# schematic.net
KiCad netlist of a schematic drawn in EAGLE
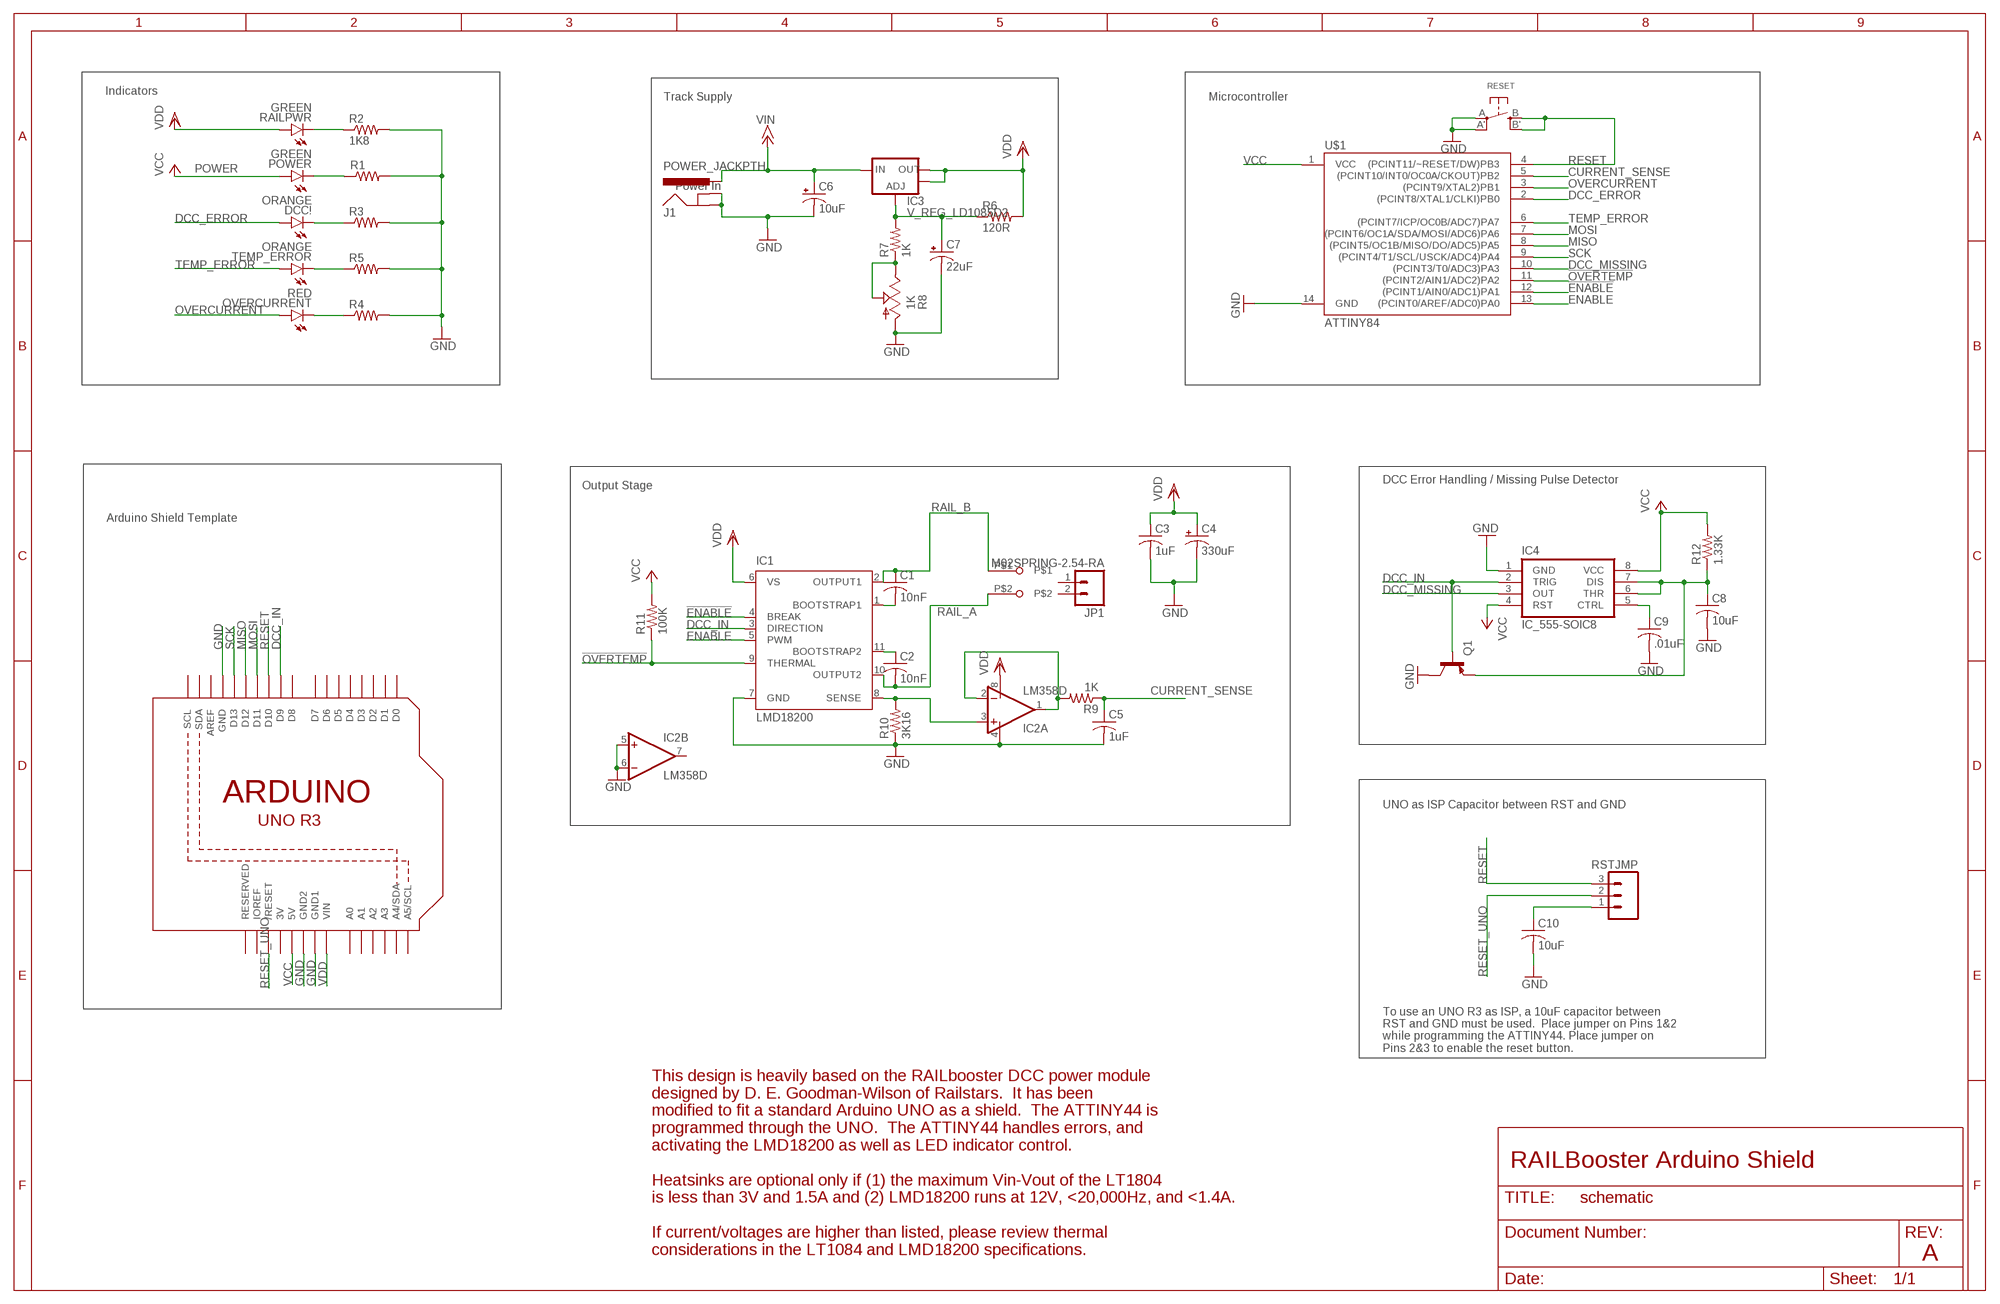
[diagram p0: schematic, sheet 1]

(export (version "E")
  (design (tool "Eeschema 10.0.6"))
  (components
    (comp (ref "C1")
      (value "10nF")
      (footprint "eagle-import:C1206")
      (libsource (lib "eagle-import") (part "C-USC1206"))
    )
    (comp (ref "C2")
      (value "10nF")
      (footprint "eagle-import:C1206")
      (libsource (lib "eagle-import") (part "C-USC1206"))
    )
    (comp (ref "C3")
      (value "1uF")
      (footprint "eagle-import:C1206")
      (libsource (lib "eagle-import") (part "C-USC1206"))
    )
    (comp (ref "C4")
      (value "330uF")
      (footprint "eagle-import:E5-10,5")
      (libsource (lib "eagle-import") (part "CPOL-USE5-10.5"))
    )
    (comp (ref "C5")
      (value "1uF")
      (footprint "eagle-import:C1206")
      (libsource (lib "eagle-import") (part "C-USC1206"))
    )
    (comp (ref "C6")
      (value "10uF")
      (footprint "eagle-import:E2-5")
      (libsource (lib "eagle-import") (part "CPOL-USE2-5"))
    )
    (comp (ref "C7")
      (value "22uF")
      (footprint "eagle-import:E2-5")
      (libsource (lib "eagle-import") (part "CPOL-USE2-5"))
    )
    (comp (ref "C8")
      (value "10uF")
      (footprint "eagle-import:C1206")
      (libsource (lib "eagle-import") (part "C-USC1206"))
    )
    (comp (ref "C9")
      (value ".01uF")
      (footprint "eagle-import:C1206")
      (libsource (lib "eagle-import") (part "C-USC1206"))
    )
    (comp (ref "C10")
      (value "10uF")
      (footprint "eagle-import:C1206")
      (libsource (lib "eagle-import") (part "C-USC1206"))
    )
    (comp (ref "DCC!")
      (value "ORANGE")
      (footprint "eagle-import:LED-1206")
      (libsource (lib "eagle-import") (part "LED1206"))
    )
    (comp (ref "IC1")
      (value "LMD18200")
      (footprint "eagle-import:TO-220-11")
      (libsource (lib "eagle-import") (part "LM18200T"))
    )
    (comp (ref "IC2")
      (value "LM358D")
      (footprint "eagle-import:SO08")
      (libsource (lib "eagle-import") (part "LM358D"))
    )
    (comp (ref "IC3")
      (value "V_REG_LD1085D2")
      (footprint "eagle-import:D2PACK_A")
      (libsource (lib "eagle-import") (part "V_REG_LD1085D2"))
    )
    (comp (ref "IC4")
      (value "IC_555-SOIC8")
      (footprint "eagle-import:SOIC-8")
      (libsource (lib "eagle-import") (part "IC_555-SOIC8"))
    )
    (comp (ref "J1")
      (value "POWER_JACKPTH")
      (footprint "eagle-import:POWER_JACK_PTH")
      (libsource (lib "eagle-import") (part "POWER_JACKPTH"))
    )
    (comp (ref "JP1")
      (value "M02SPRING-2.54-RA")
      (footprint "eagle-import:SPRINGTERMINAL-2.54MM-2")
      (libsource (lib "eagle-import") (part "M02SPRING-2.54-RA"))
    )
    (comp (ref "OVERCURRENT")
      (value "RED")
      (footprint "eagle-import:LED-1206")
      (libsource (lib "eagle-import") (part "LED1206"))
    )
    (comp (ref "POWER")
      (value "GREEN")
      (footprint "eagle-import:LED-1206")
      (libsource (lib "eagle-import") (part "LED1206"))
    )
    (comp (ref "Q1")
      (value "TRANSISTOR_BJT_PNP-SOT-23-BCE")
      (footprint "eagle-import:SOT-23")
      (libsource (lib "eagle-import") (part "TRANSISTOR_BJT_PNP-SOT-23-BCE"))
    )
    (comp (ref "R1")
      (value "RESISTOR1206")
      (footprint "eagle-import:1206")
      (libsource (lib "eagle-import") (part "RESISTOR1206"))
    )
    (comp (ref "R2")
      (value "1K8")
      (footprint "eagle-import:1206")
      (libsource (lib "eagle-import") (part "RESISTOR1206"))
    )
    (comp (ref "R3")
      (value "RESISTOR1206")
      (footprint "eagle-import:1206")
      (libsource (lib "eagle-import") (part "RESISTOR1206"))
    )
    (comp (ref "R4")
      (value "RESISTOR1206")
      (footprint "eagle-import:1206")
      (libsource (lib "eagle-import") (part "RESISTOR1206"))
    )
    (comp (ref "R5")
      (value "RESISTOR1206")
      (footprint "eagle-import:1206")
      (libsource (lib "eagle-import") (part "RESISTOR1206"))
    )
    (comp (ref "R6")
      (value "120R")
      (footprint "eagle-import:1206")
      (libsource (lib "eagle-import") (part "RESISTOR1206"))
    )
    (comp (ref "R7")
      (value "1K")
      (footprint "eagle-import:1206")
      (libsource (lib "eagle-import") (part "RESISTOR1206"))
    )
    (comp (ref "R8")
      (value "1K")
      (footprint "eagle-import:S64W")
      (libsource (lib "eagle-import") (part "TRIM_US-S64W"))
    )
    (comp (ref "R9")
      (value "1K")
      (footprint "eagle-import:1206")
      (libsource (lib "eagle-import") (part "RESISTOR1206"))
    )
    (comp (ref "R10")
      (value "3K16")
      (footprint "eagle-import:1206")
      (libsource (lib "eagle-import") (part "RESISTOR1206"))
    )
    (comp (ref "R11")
      (value "100K")
      (footprint "eagle-import:1206")
      (libsource (lib "eagle-import") (part "RESISTOR1206"))
    )
    (comp (ref "R12")
      (value "1.33K")
      (footprint "eagle-import:1206")
      (libsource (lib "eagle-import") (part "RESISTOR1206"))
    )
    (comp (ref "RAILPWR")
      (value "GREEN")
      (footprint "eagle-import:LED-1206")
      (libsource (lib "eagle-import") (part "LED1206"))
    )
    (comp (ref "RESET")
      (value "SWITCH_TACT_SMT")
      (footprint "eagle-import:EVQ-Q2")
      (libsource (lib "eagle-import") (part "SWITCH_TACT_SMT"))
    )
    (comp (ref "RSTJMP")
      (value "M03PTH")
      (footprint "eagle-import:1X03")
      (libsource (lib "eagle-import") (part "M03PTH"))
    )
    (comp (ref "TEMP_ERROR")
      (value "ORANGE")
      (footprint "eagle-import:LED-1206")
      (libsource (lib "eagle-import") (part "LED1206"))
    )
    (comp (ref "U$1")
      (value "ATTINY84")
      (footprint "eagle-import:SO14")
      (libsource (lib "eagle-import") (part "ATTINY84"))
    )
    (comp (ref "U1")
      (value "ARDUINOR3-DIMENSION")
      (footprint "eagle-import:ARDUINOR3")
      (libsource (lib "eagle-import") (part "ARDUINOR3-DIMENSION"))
    )
    (comp (ref "X4")
      (value "SCREWTERMINAL-5.08-2")
      (footprint "eagle-import:SCREWTERMINAL-5.08-2")
      (libsource (lib "eagle-import") (part "SCREWTERMINAL-5.08-2"))
    )
  )
  (nets
    (net (code "1") (name "/3V") (class "Default")
      (node (ref "U1") (pin "3V") (pinfunction "3V_3V") (pintype "power_in"))
    )
    (net (code "2") (name "/CURRENT_SENSE") (class "Default")
      (node (ref "C5") (pin "1") (pinfunction "1_1") (pintype "passive"))
      (node (ref "R9") (pin "1") (pinfunction "1_1") (pintype "passive"))
      (node (ref "U$1") (pin "5") (pinfunction "(PCINT10/INT0/OC0A/CKOUT)PB2_5") (pintype "bidirectional"))
    )
    (net (code "3") (name "/DCC_ERROR") (class "Default")
      (node (ref "DCC!") (pin "A") (pinfunction "A_A") (pintype "passive"))
      (node (ref "U$1") (pin "2") (pinfunction "(PCINT8/XTAL1/CLKI)PB0_2") (pintype "bidirectional"))
    )
    (net (code "4") (name "/DCC_IN") (class "Default")
      (node (ref "IC1") (pin "3") (pinfunction "DIRECTION_3") (pintype "input"))
      (node (ref "IC4") (pin "2") (pinfunction "TRIG_2") (pintype "input"))
      (node (ref "Q1") (pin "1") (pinfunction "B_1") (pintype "passive"))
      (node (ref "U1") (pin "D9") (pinfunction "D9_D9") (pintype "bidirectional"))
    )
    (net (code "5") (name "/DCC_MISSING") (class "Default")
      (node (ref "IC4") (pin "3") (pinfunction "OUT_3") (pintype "output"))
      (node (ref "U$1") (pin "10") (pinfunction "(PCINT3/T0/ADC3)PA3_10") (pintype "bidirectional"))
    )
    (net (code "6") (name "/ENABLE") (class "Default")
      (node (ref "IC1") (pin "5") (pinfunction "PWM_5") (pintype "input"))
      (node (ref "U$1") (pin "13") (pinfunction "(PCINT0/AREF/ADC0)PA0_13") (pintype "bidirectional"))
    )
    (net (code "7") (name "/MISO") (class "Default")
      (node (ref "U$1") (pin "8") (pinfunction "(PCINT5/OC1B/MISO/DO/ADC5)PA5_8") (pintype "bidirectional"))
      (node (ref "U1") (pin "D12") (pinfunction "D12_D12") (pintype "bidirectional"))
    )
    (net (code "8") (name "/MOSI") (class "Default")
      (node (ref "U$1") (pin "7") (pinfunction "(PCINT6/OC1A/SDA/MOSI/ADC6)PA6_7") (pintype "bidirectional"))
      (node (ref "U1") (pin "D11") (pinfunction "D11_D11") (pintype "bidirectional"))
    )
    (net (code "9") (name "/OVERCURRENT") (class "Default")
      (node (ref "OVERCURRENT") (pin "A") (pinfunction "A_A") (pintype "passive"))
      (node (ref "U$1") (pin "3") (pinfunction "(PCINT9/XTAL2)PB1_3") (pintype "bidirectional"))
    )
    (net (code "10") (name "/RAIL_A") (class "Default")
      (node (ref "C2") (pin "2") (pinfunction "2_2") (pintype "passive"))
      (node (ref "IC1") (pin "10") (pinfunction "OUTPUT2_10") (pintype "output"))
      (node (ref "X4") (pin "P$2") (pinfunction "P$2_P$2") (pintype "bidirectional"))
    )
    (net (code "11") (name "/RAIL_B") (class "Default")
      (node (ref "C1") (pin "1") (pinfunction "1_1") (pintype "passive"))
      (node (ref "IC1") (pin "2") (pinfunction "OUTPUT1_2") (pintype "output"))
      (node (ref "X4") (pin "P$1") (pinfunction "P$1_P$1") (pintype "bidirectional"))
    )
    (net (code "12") (name "/RESET") (class "Default")
      (node (ref "RESET") (pin "B") (pinfunction "S_B") (pintype "passive"))
      (node (ref "RESET") (pin "B'") (pinfunction "S1_B'") (pintype "passive"))
      (node (ref "RSTJMP") (pin "3") (pinfunction "3_3") (pintype "passive"))
      (node (ref "U$1") (pin "4") (pinfunction "(PCINT11/~{RESET/DW})PB3_4") (pintype "bidirectional"))
      (node (ref "U1") (pin "D10") (pinfunction "D10_D10") (pintype "bidirectional"))
    )
    (net (code "13") (name "/RESET_UNO") (class "Default")
      (node (ref "RSTJMP") (pin "2") (pinfunction "2_2") (pintype "passive"))
      (node (ref "U1") (pin "RESET") (pinfunction "/RESET_RESET") (pintype "bidirectional"))
    )
    (net (code "14") (name "/SCK") (class "Default")
      (node (ref "U$1") (pin "9") (pinfunction "(PCINT4/T1/SCL/USCK/ADC4)PA4_9") (pintype "bidirectional"))
      (node (ref "U1") (pin "D13") (pinfunction "D13_D13") (pintype "bidirectional"))
    )
    (net (code "15") (name "/TEMP_ERROR") (class "Default")
      (node (ref "TEMP_ERROR") (pin "A") (pinfunction "A_A") (pintype "passive"))
      (node (ref "U$1") (pin "6") (pinfunction "(PCINT7/ICP/OC0B/ADC7)PA7_6") (pintype "bidirectional"))
    )
    (net (code "16") (name "/~{ENABLE}") (class "Default")
      (node (ref "IC1") (pin "4") (pinfunction "BREAK_4") (pintype "input"))
      (node (ref "U$1") (pin "12") (pinfunction "(PCINT1/AIN0/ADC1)PA1_12") (pintype "bidirectional"))
    )
    (net (code "17") (name "/~{OVERTEMP}") (class "Default")
      (node (ref "IC1") (pin "9") (pinfunction "THERMAL_9") (pintype "output"))
      (node (ref "R11") (pin "1") (pinfunction "1_1") (pintype "passive"))
      (node (ref "U$1") (pin "11") (pinfunction "(PCINT2/AIN1/ADC2)PA2_11") (pintype "bidirectional"))
    )
    (net (code "18") (name "GND") (class "Default")
      (node (ref "C10") (pin "2") (pinfunction "2_2") (pintype "passive"))
      (node (ref "C3") (pin "2") (pinfunction "2_2") (pintype "passive"))
      (node (ref "C4") (pin "-") (pinfunction "-_-") (pintype "passive"))
      (node (ref "C5") (pin "2") (pinfunction "2_2") (pintype "passive"))
      (node (ref "C6") (pin "-") (pinfunction "-_-") (pintype "passive"))
      (node (ref "C7") (pin "-") (pinfunction "-_-") (pintype "passive"))
      (node (ref "C8") (pin "2") (pinfunction "2_2") (pintype "passive"))
      (node (ref "C9") (pin "2") (pinfunction "2_2") (pintype "passive"))
      (node (ref "IC1") (pin "7") (pinfunction "GND_7") (pintype "power_in"))
      (node (ref "IC2") (pin "4") (pinfunction "V-_4") (pintype "power_in"))
      (node (ref "IC2") (pin "5") (pinfunction "+IN_5") (pintype "input"))
      (node (ref "IC2") (pin "6") (pinfunction "-IN_6") (pintype "input"))
      (node (ref "IC4") (pin "1") (pinfunction "GND_1") (pintype "power_in"))
      (node (ref "J1") (pin "GND") (pinfunction "GND_GND") (pintype "bidirectional"))
      (node (ref "J1") (pin "GNDBREAK") (pinfunction "GNDBREAK_GNDBREAK") (pintype "bidirectional"))
      (node (ref "Q1") (pin "2") (pinfunction "C_2") (pintype "passive"))
      (node (ref "R1") (pin "2") (pinfunction "2_2") (pintype "passive"))
      (node (ref "R10") (pin "1") (pinfunction "1_1") (pintype "passive"))
      (node (ref "R2") (pin "2") (pinfunction "2_2") (pintype "passive"))
      (node (ref "R3") (pin "2") (pinfunction "2_2") (pintype "passive"))
      (node (ref "R4") (pin "2") (pinfunction "2_2") (pintype "passive"))
      (node (ref "R5") (pin "2") (pinfunction "2_2") (pintype "passive"))
      (node (ref "R8") (pin "A") (pinfunction "A_A") (pintype "passive"))
      (node (ref "RESET") (pin "A") (pinfunction "P_A") (pintype "passive"))
      (node (ref "RESET") (pin "A'") (pinfunction "P1_A'") (pintype "passive"))
      (node (ref "U$1") (pin "14") (pinfunction "GND_14") (pintype "bidirectional"))
      (node (ref "U1") (pin "GND") (pinfunction "GND_GND") (pintype "power_in"))
      (node (ref "U1") (pin "GND1") (pinfunction "GND1_GND1") (pintype "power_in"))
      (node (ref "U1") (pin "GND2") (pinfunction "GND2_GND2") (pintype "power_in"))
    )
    (net (code "19") (name "Net-(C10-Pad1)") (class "Default")
      (node (ref "C10") (pin "1") (pinfunction "1_1") (pintype "passive"))
      (node (ref "RSTJMP") (pin "1") (pinfunction "1_1") (pintype "passive"))
    )
    (net (code "20") (name "Net-(DCC!-PadC)") (class "Default")
      (node (ref "DCC!") (pin "C") (pinfunction "C_C") (pintype "passive"))
      (node (ref "R3") (pin "1") (pinfunction "1_1") (pintype "passive"))
    )
    (net (code "21") (name "Net-(IC1-BOOTSTRAP1)") (class "Default")
      (node (ref "C1") (pin "2") (pinfunction "2_2") (pintype "passive"))
      (node (ref "IC1") (pin "1") (pinfunction "BOOTSTRAP1_1") (pintype "input"))
    )
    (net (code "22") (name "Net-(IC1-BOOTSTRAP2)") (class "Default")
      (node (ref "C2") (pin "1") (pinfunction "1_1") (pintype "passive"))
      (node (ref "IC1") (pin "11") (pinfunction "BOOTSTRAP2_11") (pintype "input"))
    )
    (net (code "23") (name "Net-(IC1-SENSE)") (class "Default")
      (node (ref "IC1") (pin "8") (pinfunction "SENSE_8") (pintype "output"))
      (node (ref "IC2") (pin "3") (pinfunction "+IN_3") (pintype "input"))
      (node (ref "R10") (pin "2") (pinfunction "2_2") (pintype "passive"))
    )
    (net (code "24") (name "Net-(IC2A--IN)") (class "Default")
      (node (ref "IC2") (pin "1") (pinfunction "OUT_1") (pintype "output"))
      (node (ref "IC2") (pin "2") (pinfunction "-IN_2") (pintype "input"))
      (node (ref "R9") (pin "2") (pinfunction "2_2") (pintype "passive"))
    )
    (net (code "25") (name "Net-(IC3-ADJ)") (class "Default")
      (node (ref "C7") (pin "+") (pinfunction "+_+") (pintype "passive"))
      (node (ref "IC3") (pin "1") (pinfunction "ADJ_1") (pintype "input"))
      (node (ref "R6") (pin "1") (pinfunction "1_1") (pintype "passive"))
      (node (ref "R7") (pin "2") (pinfunction "2_2") (pintype "passive"))
    )
    (net (code "26") (name "Net-(IC4-CTRL)") (class "Default")
      (node (ref "C9") (pin "1") (pinfunction "1_1") (pintype "passive"))
      (node (ref "IC4") (pin "5") (pinfunction "CTRL_5") (pintype "power_in"))
    )
    (net (code "27") (name "Net-(IC4-DIS)") (class "Default")
      (node (ref "C8") (pin "1") (pinfunction "1_1") (pintype "passive"))
      (node (ref "IC4") (pin "6") (pinfunction "THR_6") (pintype "input"))
      (node (ref "IC4") (pin "7") (pinfunction "DIS_7") (pintype "input"))
      (node (ref "Q1") (pin "3") (pinfunction "E_3") (pintype "passive"))
      (node (ref "R12") (pin "1") (pinfunction "1_1") (pintype "passive"))
    )
    (net (code "28") (name "Net-(OVERCURRENT-PadC)") (class "Default")
      (node (ref "OVERCURRENT") (pin "C") (pinfunction "C_C") (pintype "passive"))
      (node (ref "R4") (pin "1") (pinfunction "1_1") (pintype "passive"))
    )
    (net (code "29") (name "Net-(POWER-PadC)") (class "Default")
      (node (ref "POWER") (pin "C") (pinfunction "C_C") (pintype "passive"))
      (node (ref "R1") (pin "1") (pinfunction "1_1") (pintype "passive"))
    )
    (net (code "30") (name "Net-(R2-Pad1)") (class "Default")
      (node (ref "R2") (pin "1") (pinfunction "1_1") (pintype "passive"))
      (node (ref "RAILPWR") (pin "C") (pinfunction "C_C") (pintype "passive"))
    )
    (net (code "31") (name "Net-(R5-Pad1)") (class "Default")
      (node (ref "R5") (pin "1") (pinfunction "1_1") (pintype "passive"))
      (node (ref "TEMP_ERROR") (pin "C") (pinfunction "C_C") (pintype "passive"))
    )
    (net (code "32") (name "Net-(R7-Pad1)") (class "Default")
      (node (ref "R7") (pin "1") (pinfunction "1_1") (pintype "passive"))
      (node (ref "R8") (pin "E") (pinfunction "E_E") (pintype "passive"))
      (node (ref "R8") (pin "S") (pinfunction "S_S") (pintype "passive"))
    )
    (net (code "33") (name "VCC") (class "Default")
      (node (ref "IC4") (pin "4") (pinfunction "RST_4") (pintype "input"))
      (node (ref "IC4") (pin "8") (pinfunction "VCC_8") (pintype "power_in"))
      (node (ref "POWER") (pin "A") (pinfunction "A_A") (pintype "passive"))
      (node (ref "R11") (pin "2") (pinfunction "2_2") (pintype "passive"))
      (node (ref "R12") (pin "2") (pinfunction "2_2") (pintype "passive"))
      (node (ref "U$1") (pin "1") (pinfunction "VCC_1") (pintype "bidirectional"))
      (node (ref "U1") (pin "5V") (pinfunction "5V_5V") (pintype "power_in"))
    )
    (net (code "34") (name "VDD") (class "Default")
      (node (ref "C3") (pin "1") (pinfunction "1_1") (pintype "passive"))
      (node (ref "C4") (pin "+") (pinfunction "+_+") (pintype "passive"))
      (node (ref "IC1") (pin "6") (pinfunction "VS_6") (pintype "power_in"))
      (node (ref "IC2") (pin "8") (pinfunction "V+_8") (pintype "power_in"))
      (node (ref "IC3") (pin "2") (pinfunction "OUT_2") (pintype "output"))
      (node (ref "IC3") (pin "TAB") (pinfunction "OUT_TAB") (pintype "output"))
      (node (ref "R6") (pin "2") (pinfunction "2_2") (pintype "passive"))
      (node (ref "RAILPWR") (pin "A") (pinfunction "A_A") (pintype "passive"))
      (node (ref "U1") (pin "VIN") (pinfunction "VIN_VIN") (pintype "power_in"))
    )
    (net (code "35") (name "VIN") (class "Default")
      (node (ref "C6") (pin "+") (pinfunction "+_+") (pintype "passive"))
      (node (ref "IC3") (pin "3") (pinfunction "IN_3") (pintype "input"))
      (node (ref "J1") (pin "PWR") (pinfunction "PWR_PWR") (pintype "bidirectional"))
    )
    (net (code "36") (name "unconnected-(IC2B-OUT-Pad7)") (class "Default")
      (node (ref "IC2") (pin "7") (pinfunction "OUT_7") (pintype "output"))
    )
    (net (code "37") (name "unconnected-(JP1-Pad1)") (class "Default")
      (node (ref "JP1") (pin "1") (pinfunction "1_1") (pintype "passive"))
    )
    (net (code "38") (name "unconnected-(JP1-Pad2)") (class "Default")
      (node (ref "JP1") (pin "2") (pinfunction "2_2") (pintype "passive"))
    )
    (net (code "39") (name "unconnected-(U1-A4{slash}SDA-PadA4)") (class "Default")
      (node (ref "U1") (pin "A4") (pinfunction "A4/SDA_A4") (pintype "bidirectional"))
    )
    (net (code "40") (name "unconnected-(U1-A5{slash}SCL-PadA5)") (class "Default")
      (node (ref "U1") (pin "A5") (pinfunction "A5/SCL_A5") (pintype "bidirectional"))
    )
    (net (code "41") (name "unconnected-(U1-PadA0)") (class "Default")
      (node (ref "U1") (pin "A0") (pinfunction "A0_A0") (pintype "bidirectional"))
    )
    (net (code "42") (name "unconnected-(U1-PadA1)") (class "Default")
      (node (ref "U1") (pin "A1") (pinfunction "A1_A1") (pintype "bidirectional"))
    )
    (net (code "43") (name "unconnected-(U1-PadA2)") (class "Default")
      (node (ref "U1") (pin "A2") (pinfunction "A2_A2") (pintype "bidirectional"))
    )
    (net (code "44") (name "unconnected-(U1-PadA3)") (class "Default")
      (node (ref "U1") (pin "A3") (pinfunction "A3_A3") (pintype "bidirectional"))
    )
    (net (code "45") (name "unconnected-(U1-PadAREF)") (class "Default")
      (node (ref "U1") (pin "AREF") (pinfunction "AREF_AREF") (pintype "bidirectional"))
    )
    (net (code "46") (name "unconnected-(U1-PadD0)") (class "Default")
      (node (ref "U1") (pin "D0") (pinfunction "D0_D0") (pintype "bidirectional"))
    )
    (net (code "47") (name "unconnected-(U1-PadD1)") (class "Default")
      (node (ref "U1") (pin "D1") (pinfunction "D1_D1") (pintype "bidirectional"))
    )
    (net (code "48") (name "unconnected-(U1-PadD2)") (class "Default")
      (node (ref "U1") (pin "D2") (pinfunction "D2_D2") (pintype "bidirectional"))
    )
    (net (code "49") (name "unconnected-(U1-PadD3)") (class "Default")
      (node (ref "U1") (pin "D3") (pinfunction "D3_D3") (pintype "bidirectional"))
    )
    (net (code "50") (name "unconnected-(U1-PadD4)") (class "Default")
      (node (ref "U1") (pin "D4") (pinfunction "D4_D4") (pintype "bidirectional"))
    )
    (net (code "51") (name "unconnected-(U1-PadD5)") (class "Default")
      (node (ref "U1") (pin "D5") (pinfunction "D5_D5") (pintype "bidirectional"))
    )
    (net (code "52") (name "unconnected-(U1-PadD6)") (class "Default")
      (node (ref "U1") (pin "D6") (pinfunction "D6_D6") (pintype "bidirectional"))
    )
    (net (code "53") (name "unconnected-(U1-PadD7)") (class "Default")
      (node (ref "U1") (pin "D7") (pinfunction "D7_D7") (pintype "bidirectional"))
    )
    (net (code "54") (name "unconnected-(U1-PadD8)") (class "Default")
      (node (ref "U1") (pin "D8") (pinfunction "D8_D8") (pintype "bidirectional"))
    )
    (net (code "55") (name "unconnected-(U1-PadIOREF)") (class "Default")
      (node (ref "U1") (pin "IOREF") (pinfunction "IOREF_IOREF") (pintype "output"))
    )
    (net (code "56") (name "unconnected-(U1-PadRESERVED)") (class "Default")
      (node (ref "U1") (pin "RESERVED") (pinfunction "RESERVED_RESERVED") (pintype "no_connect"))
    )
    (net (code "57") (name "unconnected-(U1-PadSCL)") (class "Default")
      (node (ref "U1") (pin "SCL") (pinfunction "SCL_SCL") (pintype "bidirectional"))
    )
    (net (code "58") (name "unconnected-(U1-PadSDA)") (class "Default")
      (node (ref "U1") (pin "SDA") (pinfunction "SDA_SDA") (pintype "bidirectional"))
    )
  )
)
